# oscillators.net
KiCad netlist of a schematic drawn in Altium Designer
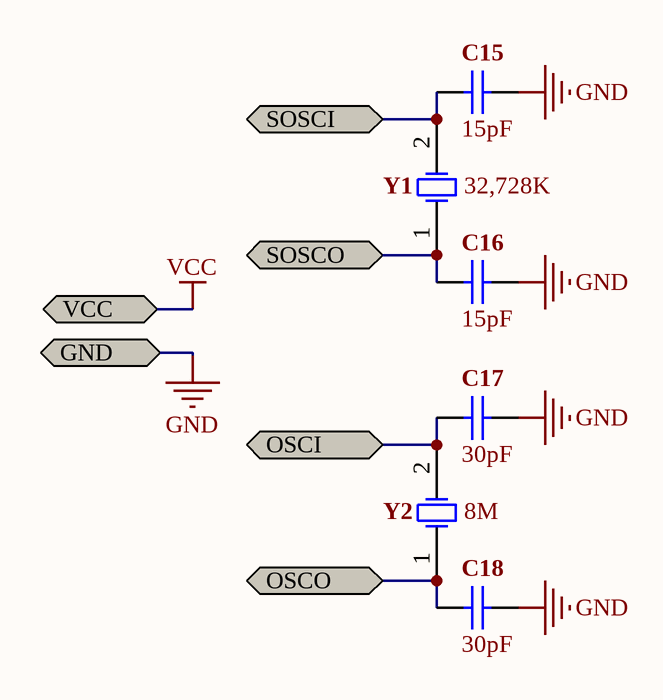
[diagram p0: oscillators.SchDoc]

(export (version "E")
  (design (tool "Eeschema 10.0.6"))
  (components
    (comp (ref "C15")
      (value "15pF")
      (footprint "1608[0603]")
      (description "Capacitor")
      (fields (field (name "Comment") "Cap") (field (name "PUBLISHER") "Altium Limited"))
      (libsource (lib "Miscellaneous Devices") (part "Cap"))
    )
    (comp (ref "C16")
      (value "15pF")
      (footprint "1608[0603]")
      (description "Capacitor")
      (fields (field (name "Comment") "Cap") (field (name "PUBLISHER") "Altium Limited"))
      (libsource (lib "Miscellaneous Devices") (part "Cap"))
    )
    (comp (ref "C17")
      (value "30pF")
      (footprint "1608[0603]")
      (description "Capacitor")
      (fields (field (name "Comment") "Cap") (field (name "PUBLISHER") "Altium Limited"))
      (libsource (lib "Miscellaneous Devices") (part "Cap"))
    )
    (comp (ref "C18")
      (value "30pF")
      (footprint "1608[0603]")
      (description "Capacitor")
      (fields (field (name "Comment") "Cap") (field (name "PUBLISHER") "Altium Limited"))
      (libsource (lib "Miscellaneous Devices") (part "Cap"))
    )
    (comp (ref "Y1")
      (value "32,728K")
      (footprint "BCY-W2/D3.1")
      (description "Crystal Oscillator")
      (fields (field (name "PUBLISHER") "Altium Limited"))
      (libsource (lib "agus_lib") (part "XTAL_2PINS"))
    )
    (comp (ref "Y2")
      (value "8M")
      (footprint "49_SMD_8Mhz")
      (description "Crystal Oscillator")
      (fields (field (name "PUBLISHER") "Altium Limited"))
      (libsource (lib "agus_lib") (part "XTAL_2PINS"))
    )
  )
  (nets
    (net (code "1") (name "/OSCI") (class "Default")
      (node (ref "C17") (pin "2") (pinfunction "2_2") (pintype "passive"))
      (node (ref "Y2") (pin "2") (pinfunction "OSC2_2") (pintype "passive"))
    )
    (net (code "2") (name "/OSCO") (class "Default")
      (node (ref "C18") (pin "2") (pinfunction "2_2") (pintype "passive"))
      (node (ref "Y2") (pin "1") (pinfunction "OSC1_1") (pintype "passive"))
    )
    (net (code "3") (name "/SOSCI") (class "Default")
      (node (ref "C15") (pin "2") (pinfunction "2_2") (pintype "passive"))
      (node (ref "Y1") (pin "2") (pinfunction "OSC2_2") (pintype "passive"))
    )
    (net (code "4") (name "/SOSCO") (class "Default")
      (node (ref "C16") (pin "2") (pinfunction "2_2") (pintype "passive"))
      (node (ref "Y1") (pin "1") (pinfunction "OSC1_1") (pintype "passive"))
    )
    (net (code "5") (name "GND") (class "Default")
      (node (ref "C15") (pin "1") (pinfunction "1_1") (pintype "passive"))
      (node (ref "C16") (pin "1") (pinfunction "1_1") (pintype "passive"))
      (node (ref "C17") (pin "1") (pinfunction "1_1") (pintype "passive"))
      (node (ref "C18") (pin "1") (pinfunction "1_1") (pintype "passive"))
    )
  )
)
